# sensor.net
KiCad netlist of a schematic drawn in EAGLE
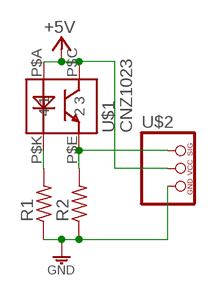
[diagram p0: schematic, sheet 1]

(export (version "E")
  (design (tool "Eeschema 10.0.6"))
  (components
    (comp (ref "R1")
      (value "RESISTORS")
      (footprint "eagle-import:R_3216")
      (libsource (lib "eagle-import") (part "RESISTORS"))
    )
    (comp (ref "R2")
      (value "RESISTORS")
      (footprint "eagle-import:R_3216")
      (libsource (lib "eagle-import") (part "RESISTORS"))
    )
    (comp (ref "U$1")
      (value "CNZ1023")
      (footprint "eagle-import:CNZ1023")
      (libsource (lib "eagle-import") (part "CNZ1023"))
    )
    (comp (ref "U$2")
      (value "PINHD-SENSOR")
      (footprint "eagle-import:1_03(KIKAKU)")
      (libsource (lib "eagle-import") (part "PINHD-SENSOR"))
    )
  )
  (nets
    (net (code "1") (name "+5V") (class "Default")
      (node (ref "U$1") (pin "P$A") (pinfunction "1_P$A") (pintype "output"))
      (node (ref "U$1") (pin "P$C") (pinfunction "3_P$C") (pintype "input"))
      (node (ref "U$2") (pin "VCC") (pinfunction "VCC_VCC") (pintype "passive"))
    )
    (net (code "2") (name "GND") (class "Default")
      (node (ref "R1") (pin "1") (pinfunction "1_1") (pintype "passive"))
      (node (ref "R2") (pin "1") (pinfunction "1_1") (pintype "passive"))
      (node (ref "U$2") (pin "GND") (pinfunction "GND_GND") (pintype "passive"))
    )
    (net (code "3") (name "Net-(U$1-2)") (class "Default")
      (node (ref "R2") (pin "2") (pinfunction "2_2") (pintype "passive"))
      (node (ref "U$1") (pin "P$E") (pinfunction "2_P$E") (pintype "output"))
      (node (ref "U$2") (pin "SIG") (pinfunction "SIG_SIG") (pintype "passive"))
    )
    (net (code "4") (name "Net-(U$1-4)") (class "Default")
      (node (ref "R1") (pin "2") (pinfunction "2_2") (pintype "passive"))
      (node (ref "U$1") (pin "P$K") (pinfunction "4_P$K") (pintype "input"))
    )
  )
)
